# Button.net
KiCad netlist of a schematic drawn in Altium Designer
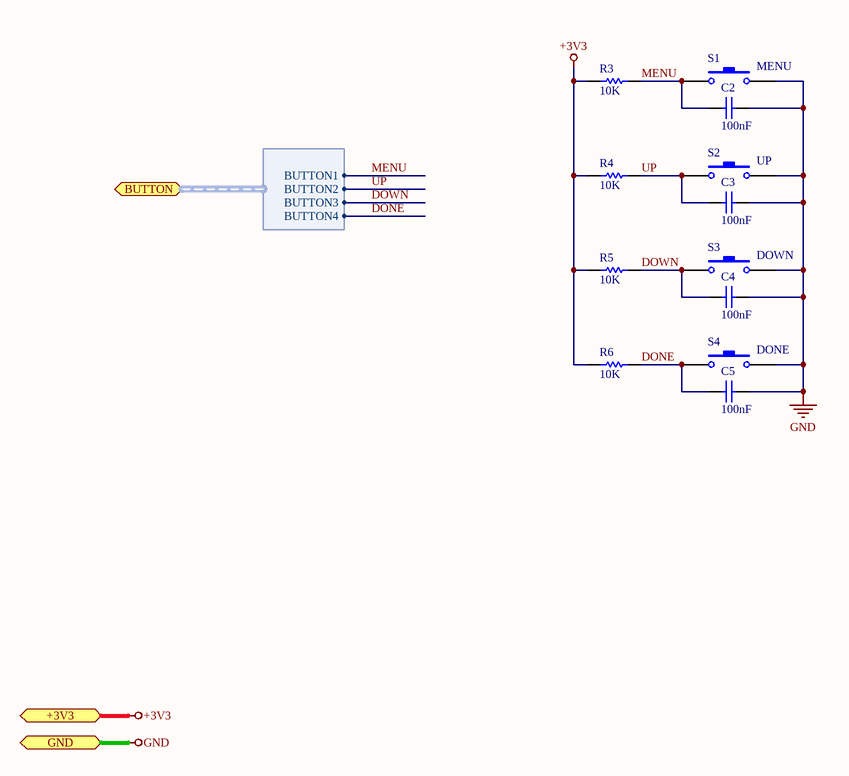
[diagram p0: Button.SchDoc]

(export (version "E")
  (design (tool "Eeschema 10.0.6"))
  (components
    (comp (ref "C2")
      (value "100nF")
      (footprint "C-0805")
      (description "Capacitor")
      (fields (field (name "Comment") "104") (field (name "PUBLISHER") "Altium Limited"))
      (libsource (lib "Miscellaneous Devices") (part "Cap"))
    )
    (comp (ref "C3")
      (value "100nF")
      (footprint "C-0805")
      (description "Capacitor")
      (fields (field (name "Comment") "104") (field (name "PUBLISHER") "Altium Limited"))
      (libsource (lib "Miscellaneous Devices") (part "Cap"))
    )
    (comp (ref "C4")
      (value "100nF")
      (footprint "C-0805")
      (description "Capacitor")
      (fields (field (name "Comment") "104") (field (name "PUBLISHER") "Altium Limited"))
      (libsource (lib "Miscellaneous Devices") (part "Cap"))
    )
    (comp (ref "C5")
      (value "100nF")
      (footprint "C-0805")
      (description "Capacitor")
      (fields (field (name "Comment") "104") (field (name "PUBLISHER") "Altium Limited"))
      (libsource (lib "Miscellaneous Devices") (part "Cap"))
    )
    (comp (ref "R3")
      (value "10K")
      (footprint "R-0805")
      (description "Resistor")
      (fields (field (name "PUBLISHER") "Altium Limited"))
      (libsource (lib "Miscellaneous Devices") (part "Res1"))
    )
    (comp (ref "R4")
      (value "10K")
      (footprint "R-0805")
      (description "Resistor")
      (fields (field (name "PUBLISHER") "Altium Limited"))
      (libsource (lib "Miscellaneous Devices") (part "Res1"))
    )
    (comp (ref "R5")
      (value "10K")
      (footprint "R-0805")
      (description "Resistor")
      (fields (field (name "PUBLISHER") "Altium Limited"))
      (libsource (lib "Miscellaneous Devices") (part "Res1"))
    )
    (comp (ref "R6")
      (value "10K")
      (footprint "R-0805")
      (description "Resistor")
      (fields (field (name "PUBLISHER") "Altium Limited"))
      (libsource (lib "Miscellaneous Devices") (part "Res1"))
    )
    (comp (ref "S1")
      (value "MENU")
      (footprint "SW-T-S12")
      (description "Switch")
      (fields (field (name "Comment") "SW-T-S12"))
      (libsource (lib "Miscellaneous Devices") (part "SW-PB"))
    )
    (comp (ref "S2")
      (value "UP")
      (footprint "SW-T-S12")
      (description "Switch")
      (fields (field (name "Comment") "SW-T-S12"))
      (libsource (lib "Miscellaneous Devices") (part "SW-PB"))
    )
    (comp (ref "S3")
      (value "DOWN")
      (footprint "SW-T-S12")
      (description "Switch")
      (fields (field (name "Comment") "SW-T-S12"))
      (libsource (lib "Miscellaneous Devices") (part "SW-PB"))
    )
    (comp (ref "S4")
      (value "DONE")
      (footprint "SW-T-S12")
      (description "Switch")
      (fields (field (name "Comment") "SW-T-S12"))
      (libsource (lib "Miscellaneous Devices") (part "SW-PB"))
    )
  )
  (nets
    (net (code "2") (name "+3V3") (class "Default")
      (node (ref "R3") (pin "2") (pinfunction "2_2") (pintype "passive"))
      (node (ref "R4") (pin "2") (pinfunction "2_2") (pintype "passive"))
      (node (ref "R5") (pin "2") (pinfunction "2_2") (pintype "passive"))
      (node (ref "R6") (pin "2") (pinfunction "2_2") (pintype "passive"))
    )
    (net (code "3") (name "/DONE") (class "Default")
      (node (ref "C5") (pin "1") (pinfunction "1_1") (pintype "passive"))
      (node (ref "R6") (pin "1") (pinfunction "1_1") (pintype "passive"))
      (node (ref "S4") (pin "1") (pinfunction "1_1") (pintype "passive"))
    )
    (net (code "4") (name "/DOWN") (class "Default")
      (node (ref "C4") (pin "1") (pinfunction "1_1") (pintype "passive"))
      (node (ref "R5") (pin "1") (pinfunction "1_1") (pintype "passive"))
      (node (ref "S3") (pin "1") (pinfunction "1_1") (pintype "passive"))
    )
    (net (code "5") (name "/MENU") (class "Default")
      (node (ref "C2") (pin "1") (pinfunction "1_1") (pintype "passive"))
      (node (ref "R3") (pin "1") (pinfunction "1_1") (pintype "passive"))
      (node (ref "S1") (pin "1") (pinfunction "1_1") (pintype "passive"))
    )
    (net (code "6") (name "/UP") (class "Default")
      (node (ref "C3") (pin "1") (pinfunction "1_1") (pintype "passive"))
      (node (ref "R4") (pin "1") (pinfunction "1_1") (pintype "passive"))
      (node (ref "S2") (pin "1") (pinfunction "1_1") (pintype "passive"))
    )
    (net (code "8") (name "GND") (class "Default")
      (node (ref "C2") (pin "2") (pinfunction "2_2") (pintype "passive"))
      (node (ref "C3") (pin "2") (pinfunction "2_2") (pintype "passive"))
      (node (ref "C4") (pin "2") (pinfunction "2_2") (pintype "passive"))
      (node (ref "C5") (pin "2") (pinfunction "2_2") (pintype "passive"))
      (node (ref "S1") (pin "2") (pinfunction "2_2") (pintype "passive"))
      (node (ref "S2") (pin "2") (pinfunction "2_2") (pintype "passive"))
      (node (ref "S3") (pin "2") (pinfunction "2_2") (pintype "passive"))
      (node (ref "S4") (pin "2") (pinfunction "2_2") (pintype "passive"))
    )
  )
)
